# QFN44-TQFP44.net
KiCad netlist of a schematic drawn in EAGLE
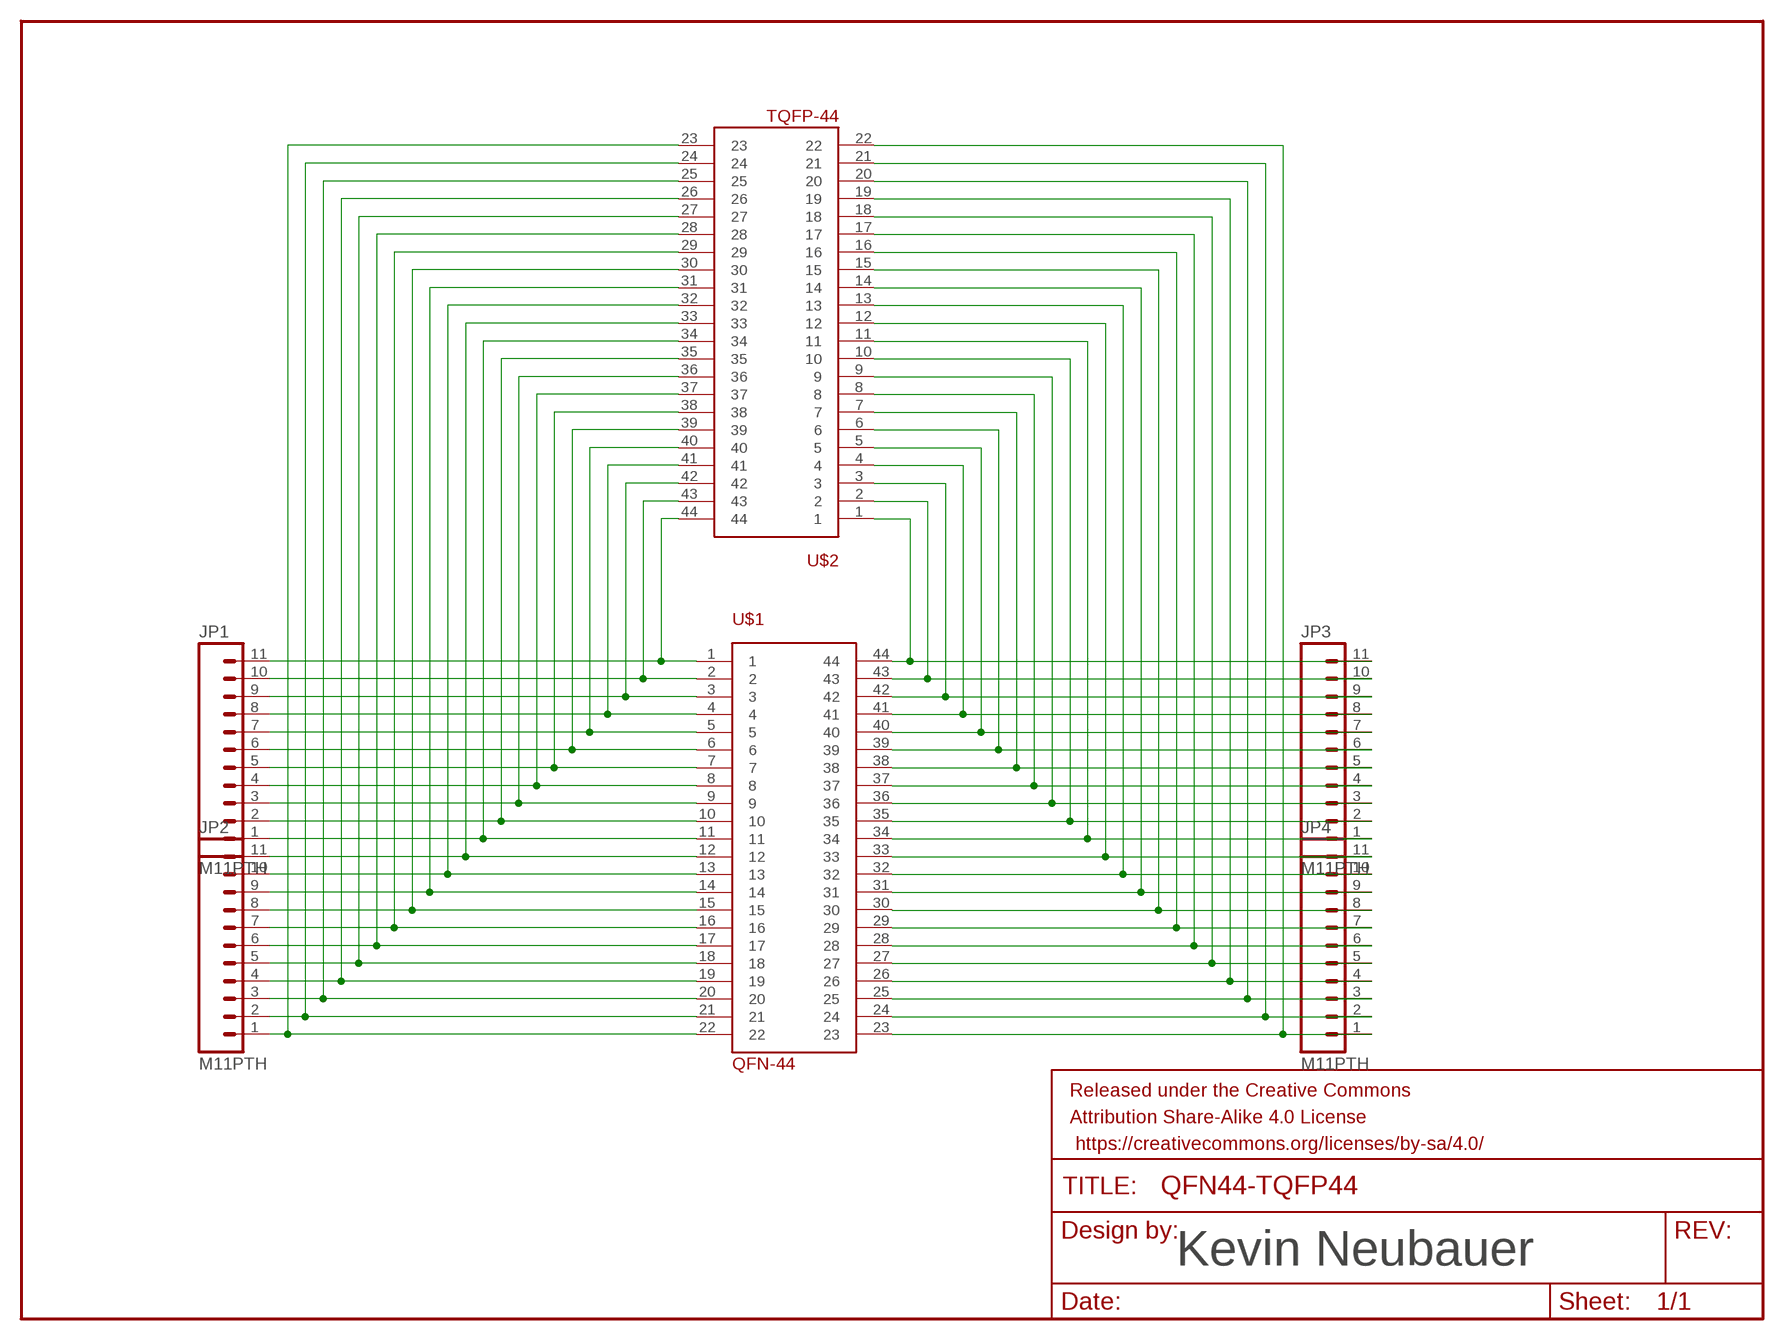
[diagram p0: schematic, sheet 1]

(export (version "E")
  (design (tool "Eeschema 10.0.6"))
  (components
    (comp (ref "FRAME1")
      (value "FRAME-LETTER")
      (footprint "eagle-import:CREATIVE_COMMONS")
      (libsource (lib "eagle-import") (part "FRAME-LETTER"))
    )
    (comp (ref "JP1")
      (value "M11PTH")
      (footprint "eagle-import:1X11")
      (libsource (lib "eagle-import") (part "M11PTH"))
    )
    (comp (ref "JP2")
      (value "M11PTH")
      (footprint "eagle-import:1X11")
      (libsource (lib "eagle-import") (part "M11PTH"))
    )
    (comp (ref "JP3")
      (value "M11PTH")
      (footprint "eagle-import:1X11")
      (libsource (lib "eagle-import") (part "M11PTH"))
    )
    (comp (ref "JP4")
      (value "M11PTH")
      (footprint "eagle-import:1X11")
      (libsource (lib "eagle-import") (part "M11PTH"))
    )
    (comp (ref "U$1")
      (value "QFN-44")
      (footprint "eagle-import:QFN-44")
      (libsource (lib "eagle-import") (part "QFN-44"))
    )
    (comp (ref "U$2")
      (value "TQFP-44")
      (footprint "eagle-import:TQFP44")
      (libsource (lib "eagle-import") (part "TQFP-44"))
    )
  )
  (nets
    (net (code "1") (name "Net-(JP1-Pad1)") (class "Default")
      (node (ref "JP1") (pin "1") (pinfunction "1_1") (pintype "passive"))
      (node (ref "U$1") (pin "11") (pinfunction "11_11") (pintype "bidirectional"))
      (node (ref "U$2") (pin "34") (pinfunction "34_34") (pintype "bidirectional"))
    )
    (net (code "2") (name "Net-(JP1-Pad2)") (class "Default")
      (node (ref "JP1") (pin "2") (pinfunction "2_2") (pintype "passive"))
      (node (ref "U$1") (pin "10") (pinfunction "10_10") (pintype "bidirectional"))
      (node (ref "U$2") (pin "35") (pinfunction "35_35") (pintype "bidirectional"))
    )
    (net (code "3") (name "Net-(JP1-Pad3)") (class "Default")
      (node (ref "JP1") (pin "3") (pinfunction "3_3") (pintype "passive"))
      (node (ref "U$1") (pin "9") (pinfunction "9_9") (pintype "bidirectional"))
      (node (ref "U$2") (pin "36") (pinfunction "36_36") (pintype "bidirectional"))
    )
    (net (code "4") (name "Net-(JP1-Pad4)") (class "Default")
      (node (ref "JP1") (pin "4") (pinfunction "4_4") (pintype "passive"))
      (node (ref "U$1") (pin "8") (pinfunction "8_8") (pintype "bidirectional"))
      (node (ref "U$2") (pin "37") (pinfunction "37_37") (pintype "bidirectional"))
    )
    (net (code "5") (name "Net-(JP1-Pad5)") (class "Default")
      (node (ref "JP1") (pin "5") (pinfunction "5_5") (pintype "passive"))
      (node (ref "U$1") (pin "7") (pinfunction "7_7") (pintype "bidirectional"))
      (node (ref "U$2") (pin "38") (pinfunction "38_38") (pintype "bidirectional"))
    )
    (net (code "6") (name "Net-(JP1-Pad6)") (class "Default")
      (node (ref "JP1") (pin "6") (pinfunction "6_6") (pintype "passive"))
      (node (ref "U$1") (pin "6") (pinfunction "6_6") (pintype "bidirectional"))
      (node (ref "U$2") (pin "39") (pinfunction "39_39") (pintype "bidirectional"))
    )
    (net (code "7") (name "Net-(JP1-Pad7)") (class "Default")
      (node (ref "JP1") (pin "7") (pinfunction "7_7") (pintype "passive"))
      (node (ref "U$1") (pin "5") (pinfunction "5_5") (pintype "bidirectional"))
      (node (ref "U$2") (pin "40") (pinfunction "40_40") (pintype "bidirectional"))
    )
    (net (code "8") (name "Net-(JP1-Pad8)") (class "Default")
      (node (ref "JP1") (pin "8") (pinfunction "8_8") (pintype "passive"))
      (node (ref "U$1") (pin "4") (pinfunction "4_4") (pintype "bidirectional"))
      (node (ref "U$2") (pin "41") (pinfunction "41_41") (pintype "bidirectional"))
    )
    (net (code "9") (name "Net-(JP1-Pad9)") (class "Default")
      (node (ref "JP1") (pin "9") (pinfunction "9_9") (pintype "passive"))
      (node (ref "U$1") (pin "3") (pinfunction "3_3") (pintype "bidirectional"))
      (node (ref "U$2") (pin "42") (pinfunction "42_42") (pintype "bidirectional"))
    )
    (net (code "10") (name "Net-(JP1-Pad10)") (class "Default")
      (node (ref "JP1") (pin "10") (pinfunction "10_10") (pintype "passive"))
      (node (ref "U$1") (pin "2") (pinfunction "2_2") (pintype "bidirectional"))
      (node (ref "U$2") (pin "43") (pinfunction "43_43") (pintype "bidirectional"))
    )
    (net (code "11") (name "Net-(JP1-Pad11)") (class "Default")
      (node (ref "JP1") (pin "11") (pinfunction "11_11") (pintype "passive"))
      (node (ref "U$1") (pin "1") (pinfunction "1_1") (pintype "bidirectional"))
      (node (ref "U$2") (pin "44") (pinfunction "44_44") (pintype "bidirectional"))
    )
    (net (code "12") (name "Net-(JP2-Pad1)") (class "Default")
      (node (ref "JP2") (pin "1") (pinfunction "1_1") (pintype "passive"))
      (node (ref "U$1") (pin "22") (pinfunction "22_22") (pintype "bidirectional"))
      (node (ref "U$2") (pin "23") (pinfunction "23_23") (pintype "bidirectional"))
    )
    (net (code "13") (name "Net-(JP2-Pad2)") (class "Default")
      (node (ref "JP2") (pin "2") (pinfunction "2_2") (pintype "passive"))
      (node (ref "U$1") (pin "21") (pinfunction "21_21") (pintype "bidirectional"))
      (node (ref "U$2") (pin "24") (pinfunction "24_24") (pintype "bidirectional"))
    )
    (net (code "14") (name "Net-(JP2-Pad3)") (class "Default")
      (node (ref "JP2") (pin "3") (pinfunction "3_3") (pintype "passive"))
      (node (ref "U$1") (pin "20") (pinfunction "20_20") (pintype "bidirectional"))
      (node (ref "U$2") (pin "25") (pinfunction "25_25") (pintype "bidirectional"))
    )
    (net (code "15") (name "Net-(JP2-Pad4)") (class "Default")
      (node (ref "JP2") (pin "4") (pinfunction "4_4") (pintype "passive"))
      (node (ref "U$1") (pin "19") (pinfunction "19_19") (pintype "bidirectional"))
      (node (ref "U$2") (pin "26") (pinfunction "26_26") (pintype "bidirectional"))
    )
    (net (code "16") (name "Net-(JP2-Pad5)") (class "Default")
      (node (ref "JP2") (pin "5") (pinfunction "5_5") (pintype "passive"))
      (node (ref "U$1") (pin "18") (pinfunction "18_18") (pintype "bidirectional"))
      (node (ref "U$2") (pin "27") (pinfunction "27_27") (pintype "bidirectional"))
    )
    (net (code "17") (name "Net-(JP2-Pad6)") (class "Default")
      (node (ref "JP2") (pin "6") (pinfunction "6_6") (pintype "passive"))
      (node (ref "U$1") (pin "17") (pinfunction "17_17") (pintype "bidirectional"))
      (node (ref "U$2") (pin "28") (pinfunction "28_28") (pintype "bidirectional"))
    )
    (net (code "18") (name "Net-(JP2-Pad7)") (class "Default")
      (node (ref "JP2") (pin "7") (pinfunction "7_7") (pintype "passive"))
      (node (ref "U$1") (pin "16") (pinfunction "16_16") (pintype "bidirectional"))
      (node (ref "U$2") (pin "29") (pinfunction "29_29") (pintype "bidirectional"))
    )
    (net (code "19") (name "Net-(JP2-Pad8)") (class "Default")
      (node (ref "JP2") (pin "8") (pinfunction "8_8") (pintype "passive"))
      (node (ref "U$1") (pin "15") (pinfunction "15_15") (pintype "bidirectional"))
      (node (ref "U$2") (pin "30") (pinfunction "30_30") (pintype "bidirectional"))
    )
    (net (code "20") (name "Net-(JP2-Pad9)") (class "Default")
      (node (ref "JP2") (pin "9") (pinfunction "9_9") (pintype "passive"))
      (node (ref "U$1") (pin "14") (pinfunction "14_14") (pintype "bidirectional"))
      (node (ref "U$2") (pin "31") (pinfunction "31_31") (pintype "bidirectional"))
    )
    (net (code "21") (name "Net-(JP2-Pad10)") (class "Default")
      (node (ref "JP2") (pin "10") (pinfunction "10_10") (pintype "passive"))
      (node (ref "U$1") (pin "13") (pinfunction "13_13") (pintype "bidirectional"))
      (node (ref "U$2") (pin "32") (pinfunction "32_32") (pintype "bidirectional"))
    )
    (net (code "22") (name "Net-(JP2-Pad11)") (class "Default")
      (node (ref "JP2") (pin "11") (pinfunction "11_11") (pintype "passive"))
      (node (ref "U$1") (pin "12") (pinfunction "12_12") (pintype "bidirectional"))
      (node (ref "U$2") (pin "33") (pinfunction "33_33") (pintype "bidirectional"))
    )
    (net (code "23") (name "Net-(JP3-Pad1)") (class "Default")
      (node (ref "JP3") (pin "1") (pinfunction "1_1") (pintype "passive"))
      (node (ref "U$1") (pin "34") (pinfunction "34_34") (pintype "bidirectional"))
      (node (ref "U$2") (pin "11") (pinfunction "11_11") (pintype "bidirectional"))
    )
    (net (code "24") (name "Net-(JP3-Pad2)") (class "Default")
      (node (ref "JP3") (pin "2") (pinfunction "2_2") (pintype "passive"))
      (node (ref "U$1") (pin "35") (pinfunction "35_35") (pintype "bidirectional"))
      (node (ref "U$2") (pin "10") (pinfunction "10_10") (pintype "bidirectional"))
    )
    (net (code "25") (name "Net-(JP3-Pad3)") (class "Default")
      (node (ref "JP3") (pin "3") (pinfunction "3_3") (pintype "passive"))
      (node (ref "U$1") (pin "36") (pinfunction "36_36") (pintype "bidirectional"))
      (node (ref "U$2") (pin "9") (pinfunction "9_9") (pintype "bidirectional"))
    )
    (net (code "26") (name "Net-(JP3-Pad4)") (class "Default")
      (node (ref "JP3") (pin "4") (pinfunction "4_4") (pintype "passive"))
      (node (ref "U$1") (pin "37") (pinfunction "37_37") (pintype "bidirectional"))
      (node (ref "U$2") (pin "8") (pinfunction "8_8") (pintype "bidirectional"))
    )
    (net (code "27") (name "Net-(JP3-Pad5)") (class "Default")
      (node (ref "JP3") (pin "5") (pinfunction "5_5") (pintype "passive"))
      (node (ref "U$1") (pin "38") (pinfunction "38_38") (pintype "bidirectional"))
      (node (ref "U$2") (pin "7") (pinfunction "7_7") (pintype "bidirectional"))
    )
    (net (code "28") (name "Net-(JP3-Pad6)") (class "Default")
      (node (ref "JP3") (pin "6") (pinfunction "6_6") (pintype "passive"))
      (node (ref "U$1") (pin "39") (pinfunction "39_39") (pintype "bidirectional"))
      (node (ref "U$2") (pin "6") (pinfunction "6_6") (pintype "bidirectional"))
    )
    (net (code "29") (name "Net-(JP3-Pad7)") (class "Default")
      (node (ref "JP3") (pin "7") (pinfunction "7_7") (pintype "passive"))
      (node (ref "U$1") (pin "40") (pinfunction "40_40") (pintype "bidirectional"))
      (node (ref "U$2") (pin "5") (pinfunction "5_5") (pintype "bidirectional"))
    )
    (net (code "30") (name "Net-(JP3-Pad8)") (class "Default")
      (node (ref "JP3") (pin "8") (pinfunction "8_8") (pintype "passive"))
      (node (ref "U$1") (pin "41") (pinfunction "41_41") (pintype "bidirectional"))
      (node (ref "U$2") (pin "4") (pinfunction "4_4") (pintype "bidirectional"))
    )
    (net (code "31") (name "Net-(JP3-Pad9)") (class "Default")
      (node (ref "JP3") (pin "9") (pinfunction "9_9") (pintype "passive"))
      (node (ref "U$1") (pin "42") (pinfunction "42_42") (pintype "bidirectional"))
      (node (ref "U$2") (pin "3") (pinfunction "3_3") (pintype "bidirectional"))
    )
    (net (code "32") (name "Net-(JP3-Pad10)") (class "Default")
      (node (ref "JP3") (pin "10") (pinfunction "10_10") (pintype "passive"))
      (node (ref "U$1") (pin "43") (pinfunction "43_43") (pintype "bidirectional"))
      (node (ref "U$2") (pin "2") (pinfunction "2_2") (pintype "bidirectional"))
    )
    (net (code "33") (name "Net-(JP3-Pad11)") (class "Default")
      (node (ref "JP3") (pin "11") (pinfunction "11_11") (pintype "passive"))
      (node (ref "U$1") (pin "44") (pinfunction "44_44") (pintype "bidirectional"))
      (node (ref "U$2") (pin "1") (pinfunction "1_1") (pintype "bidirectional"))
    )
    (net (code "34") (name "Net-(JP4-Pad1)") (class "Default")
      (node (ref "JP4") (pin "1") (pinfunction "1_1") (pintype "passive"))
      (node (ref "U$1") (pin "23") (pinfunction "23_23") (pintype "bidirectional"))
      (node (ref "U$2") (pin "22") (pinfunction "22_22") (pintype "bidirectional"))
    )
    (net (code "35") (name "Net-(JP4-Pad2)") (class "Default")
      (node (ref "JP4") (pin "2") (pinfunction "2_2") (pintype "passive"))
      (node (ref "U$1") (pin "24") (pinfunction "24_24") (pintype "bidirectional"))
      (node (ref "U$2") (pin "21") (pinfunction "21_21") (pintype "bidirectional"))
    )
    (net (code "36") (name "Net-(JP4-Pad3)") (class "Default")
      (node (ref "JP4") (pin "3") (pinfunction "3_3") (pintype "passive"))
      (node (ref "U$1") (pin "25") (pinfunction "25_25") (pintype "bidirectional"))
      (node (ref "U$2") (pin "20") (pinfunction "20_20") (pintype "bidirectional"))
    )
    (net (code "37") (name "Net-(JP4-Pad4)") (class "Default")
      (node (ref "JP4") (pin "4") (pinfunction "4_4") (pintype "passive"))
      (node (ref "U$1") (pin "26") (pinfunction "26_26") (pintype "bidirectional"))
      (node (ref "U$2") (pin "19") (pinfunction "19_19") (pintype "bidirectional"))
    )
    (net (code "38") (name "Net-(JP4-Pad5)") (class "Default")
      (node (ref "JP4") (pin "5") (pinfunction "5_5") (pintype "passive"))
      (node (ref "U$1") (pin "27") (pinfunction "27_27") (pintype "bidirectional"))
      (node (ref "U$2") (pin "18") (pinfunction "18_18") (pintype "bidirectional"))
    )
    (net (code "39") (name "Net-(JP4-Pad6)") (class "Default")
      (node (ref "JP4") (pin "6") (pinfunction "6_6") (pintype "passive"))
      (node (ref "U$1") (pin "28") (pinfunction "28_28") (pintype "bidirectional"))
      (node (ref "U$2") (pin "17") (pinfunction "17_17") (pintype "bidirectional"))
    )
    (net (code "40") (name "Net-(JP4-Pad7)") (class "Default")
      (node (ref "JP4") (pin "7") (pinfunction "7_7") (pintype "passive"))
      (node (ref "U$1") (pin "29") (pinfunction "29_29") (pintype "bidirectional"))
      (node (ref "U$2") (pin "16") (pinfunction "16_16") (pintype "bidirectional"))
    )
    (net (code "41") (name "Net-(JP4-Pad8)") (class "Default")
      (node (ref "JP4") (pin "8") (pinfunction "8_8") (pintype "passive"))
      (node (ref "U$1") (pin "30") (pinfunction "30_30") (pintype "bidirectional"))
      (node (ref "U$2") (pin "15") (pinfunction "15_15") (pintype "bidirectional"))
    )
    (net (code "42") (name "Net-(JP4-Pad9)") (class "Default")
      (node (ref "JP4") (pin "9") (pinfunction "9_9") (pintype "passive"))
      (node (ref "U$1") (pin "31") (pinfunction "31_31") (pintype "bidirectional"))
      (node (ref "U$2") (pin "14") (pinfunction "14_14") (pintype "bidirectional"))
    )
    (net (code "43") (name "Net-(JP4-Pad10)") (class "Default")
      (node (ref "JP4") (pin "10") (pinfunction "10_10") (pintype "passive"))
      (node (ref "U$1") (pin "32") (pinfunction "32_32") (pintype "bidirectional"))
      (node (ref "U$2") (pin "13") (pinfunction "13_13") (pintype "bidirectional"))
    )
    (net (code "44") (name "Net-(JP4-Pad11)") (class "Default")
      (node (ref "JP4") (pin "11") (pinfunction "11_11") (pintype "passive"))
      (node (ref "U$1") (pin "33") (pinfunction "33_33") (pintype "bidirectional"))
      (node (ref "U$2") (pin "12") (pinfunction "12_12") (pintype "bidirectional"))
    )
  )
)
